# Safety_Loops.net
KiCad netlist of a schematic drawn in Altium Designer
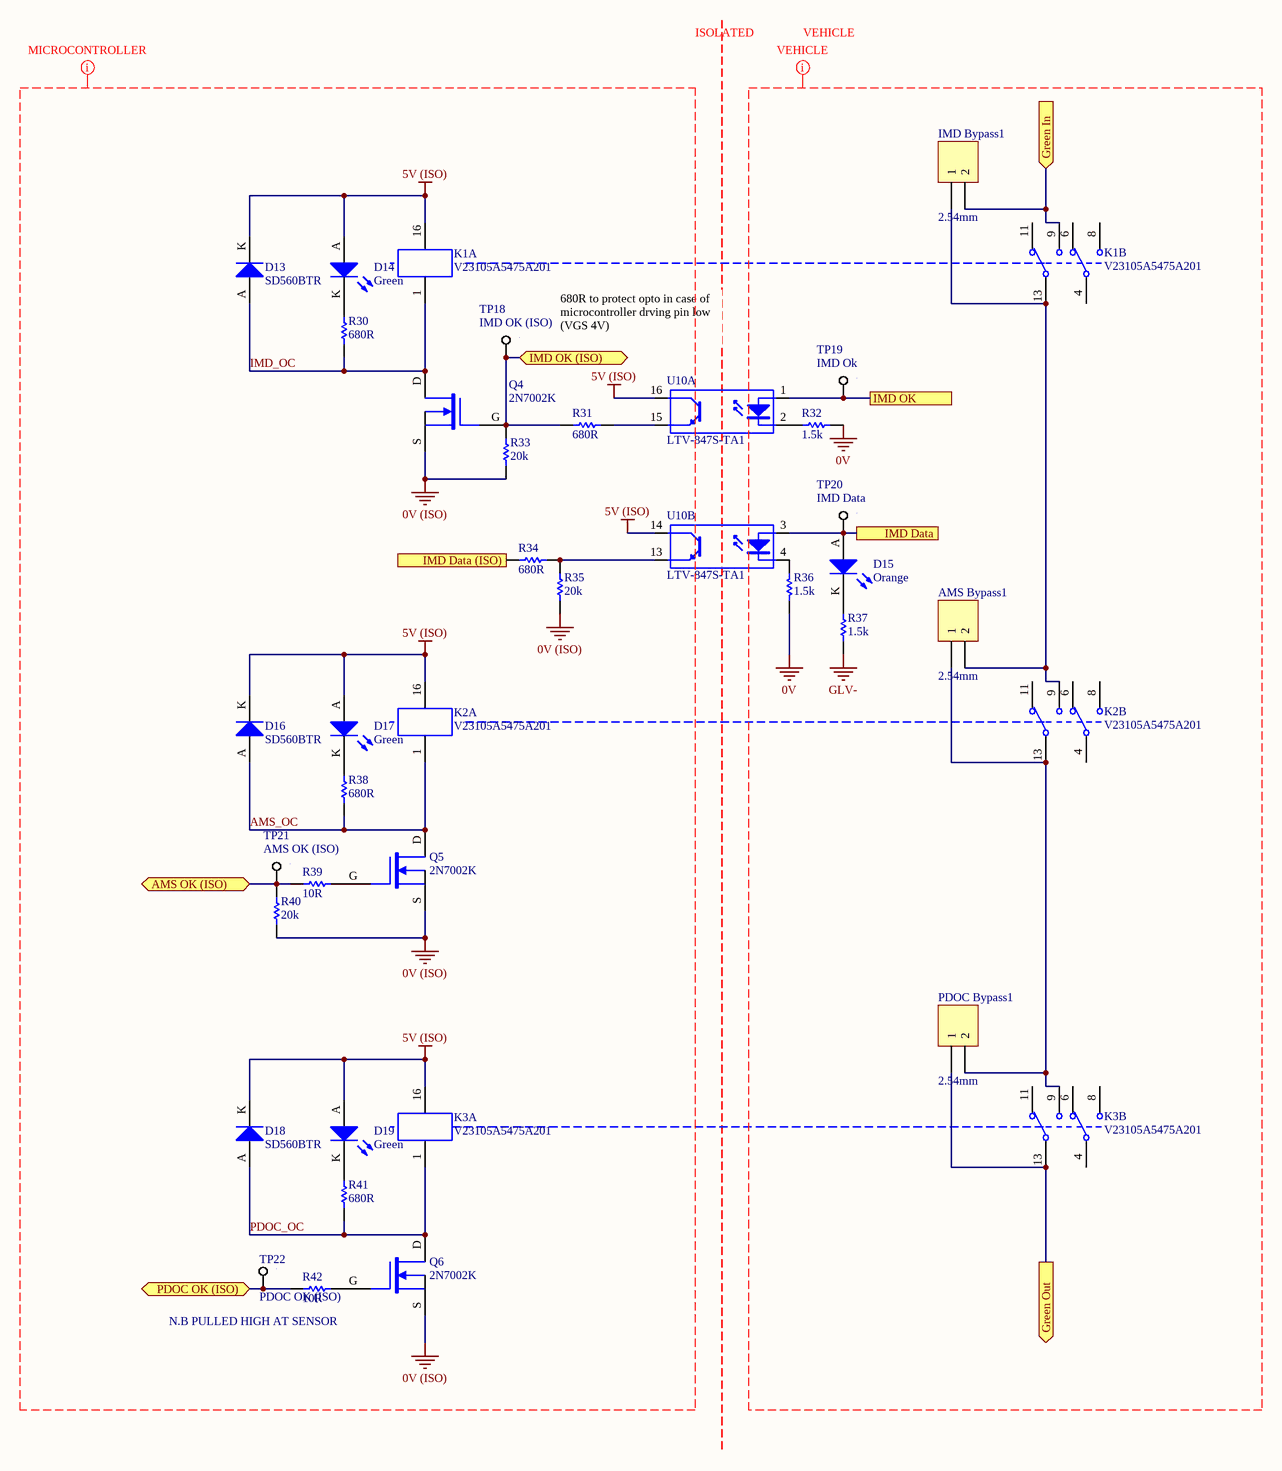
[diagram p0: Safety Loops.SchDoc]

(export (version "E")
  (design (tool "Eeschema 10.0.6"))
  (components
    (comp (ref "AMS Bypass1")
      (value "2.54mm")
      (footprint "TH 2.54mm Header 1x2")
      (fields (field (name "PART NUMBER") "TH 2.54mm Header 1x2") (field (name "CONTACT") "NA"))
      (libsource (lib "ts_20-standard-connectors") (part "Header 1x2"))
    )
    (comp (ref "D13")
      (value "SD560BTR")
      (footprint "SMB Diode")
      (description "1.2V_F 600V 5A SMB")
      (fields
        (field (name "MANUFACTURER") "SMC Diode Solutions")
        (field (name "DIGIKEY PART NUMBER") "1655-1530-2-ND")
      )
      (libsource (lib "ts_20-standard-library") (part "Diode"))
    )
    (comp (ref "D14")
      (value "Green")
      (footprint "0805 LED")
      (description "Green LED Indication - Discrete 1.75V 0805 (2012 Metric)")
      (fields (field (name "PART NUMBER") "SML-210FTT86") (field (name "MANUFACTURER") "ROHM Semiconductor"))
      (libsource (lib "ts_20-standard-library") (part "LED"))
    )
    (comp (ref "D15")
      (value "Orange")
      (footprint "0805 LED")
      (description "Orange LED Indication - Discrete 1.75V 0805 (2012 Metric)")
      (fields (field (name "PART NUMBER") "SML-211DTT86") (field (name "MANUFACTURER") "ROHM Semiconductor"))
      (libsource (lib "ts_20-standard-library") (part "LED"))
    )
    (comp (ref "D16")
      (value "SD560BTR")
      (footprint "SMB Diode")
      (description "1.2V_F 600V 5A SMB")
      (fields
        (field (name "MANUFACTURER") "SMC Diode Solutions")
        (field (name "DIGIKEY PART NUMBER") "1655-1530-2-ND")
      )
      (libsource (lib "ts_20-standard-library") (part "Diode"))
    )
    (comp (ref "D17")
      (value "Green")
      (footprint "0805 LED")
      (description "Green LED Indication - Discrete 1.75V 0805 (2012 Metric)")
      (fields (field (name "PART NUMBER") "SML-210FTT86") (field (name "MANUFACTURER") "ROHM Semiconductor"))
      (libsource (lib "ts_20-standard-library") (part "LED"))
    )
    (comp (ref "D18")
      (value "SD560BTR")
      (footprint "SMB Diode")
      (description "1.2V_F 600V 5A SMB")
      (fields
        (field (name "MANUFACTURER") "SMC Diode Solutions")
        (field (name "DIGIKEY PART NUMBER") "1655-1530-2-ND")
      )
      (libsource (lib "ts_20-standard-library") (part "Diode"))
    )
    (comp (ref "D19")
      (value "Green")
      (footprint "0805 LED")
      (description "Green LED Indication - Discrete 1.75V 0805 (2012 Metric)")
      (fields (field (name "PART NUMBER") "SML-210FTT86") (field (name "MANUFACTURER") "ROHM Semiconductor"))
      (libsource (lib "ts_20-standard-library") (part "LED"))
    )
    (comp (ref "IMD Bypass1")
      (value "2.54mm")
      (footprint "TH 2.54mm Header 1x2")
      (fields (field (name "PART NUMBER") "TH 2.54mm Header 1x2") (field (name "CONTACT") "NA"))
      (libsource (lib "ts_20-standard-connectors") (part "Header 1x2"))
    )
    (comp (ref "K1")
      (value "V23105A5475A201")
      (footprint "TI 2-DIL")
      (description "5V DPDT Relay 3A 220VDC")
      (fields (field (name "MANUFACTURER") "Axicom") (field (name "DIGIKEY PART NUMBER") "PB383-ND"))
      (libsource (lib "") (part "V23105A5475A201_1"))
    )
    (comp (ref "K2")
      (value "V23105A5475A201")
      (footprint "TI 2-DIL")
      (description "5V DPDT Relay 3A 220VDC")
      (fields (field (name "MANUFACTURER") "Axicom") (field (name "DIGIKEY PART NUMBER") "PB383-ND"))
      (libsource (lib "ts_20-standard-library") (part "V23105A5475A201"))
    )
    (comp (ref "K3")
      (value "V23105A5475A201")
      (footprint "TI 2-DIL")
      (description "5V DPDT Relay 3A 220VDC")
      (fields (field (name "MANUFACTURER") "Axicom") (field (name "DIGIKEY PART NUMBER") "PB383-ND"))
      (libsource (lib "ts_20-standard-library") (part "V23105A5475A201"))
    )
    (comp (ref "PDOC Bypass1")
      (value "2.54mm")
      (footprint "TH 2.54mm Header 1x2")
      (fields (field (name "PART NUMBER") "TH 2.54mm Header 1x2") (field (name "CONTACT") "NA"))
      (libsource (lib "ts_20-standard-connectors") (part "Header 1x2"))
    )
    (comp (ref "Q4")
      (value "2N7002K")
      (footprint "ON SOT-23 MOSFET")
      (description "60V 380mA, NFET MOSTFET (Small Signal)")
      (fields
        (field (name "MANUFACTURER") "ON Semiconductor")
        (field (name "DIGIKEY PART NUMBER") "2N7002KCT-ND")
        (field (name "PUBLISHER") "Altium Limited")
      )
      (libsource (lib "ts_20-standard-library") (part "MOSFET-N"))
    )
    (comp (ref "Q5")
      (value "2N7002K")
      (footprint "ON SOT-23 MOSFET")
      (description "60V 380mA, NFET MOSTFET (Small Signal)")
      (fields
        (field (name "MANUFACTURER") "ON Semiconductor")
        (field (name "DIGIKEY PART NUMBER") "2N7002KCT-ND")
        (field (name "PUBLISHER") "Altium Limited")
      )
      (libsource (lib "ts_20-standard-library") (part "MOSFET-N"))
    )
    (comp (ref "Q6")
      (value "2N7002K")
      (footprint "ON SOT-23 MOSFET")
      (description "60V 380mA, NFET MOSTFET (Small Signal)")
      (fields
        (field (name "MANUFACTURER") "ON Semiconductor")
        (field (name "DIGIKEY PART NUMBER") "2N7002KCT-ND")
        (field (name "PUBLISHER") "Altium Limited")
      )
      (libsource (lib "ts_20-standard-library") (part "MOSFET-N"))
    )
    (comp (ref "R30")
      (value "680R")
      (footprint "0805")
      (fields
        (field (name "PART NUMBER") "RC0805FR07680RL")
        (field (name "MANUFACTURER") "YAGEO")
        (field (name "TOLERANCE") "0.01")
      )
      (libsource (lib "ts_20-standard-library") (part "Resistor"))
    )
    (comp (ref "R31")
      (value "680R")
      (footprint "0805")
      (fields
        (field (name "PART NUMBER") "RC0805FR07680RL")
        (field (name "MANUFACTURER") "YAGEO")
        (field (name "TOLERANCE") "0.01")
      )
      (libsource (lib "ts_20-standard-library") (part "Resistor"))
    )
    (comp (ref "R32")
      (value "1.5k")
      (footprint "0805")
      (fields
        (field (name "PART NUMBER") "RC0805FR071K5L")
        (field (name "MANUFACTURER") "YAGEO")
        (field (name "TOLERANCE") "0.01")
      )
      (libsource (lib "ts_20-standard-library") (part "Resistor"))
    )
    (comp (ref "R33")
      (value "20k")
      (footprint "0805")
      (fields
        (field (name "PART NUMBER") "RC0805FR0720KL")
        (field (name "MANUFACTURER") "YAGEO")
        (field (name "TOLERANCE") "0.01")
      )
      (libsource (lib "ts_20-standard-library") (part "Resistor"))
    )
    (comp (ref "R34")
      (value "680R")
      (footprint "0805")
      (fields
        (field (name "PART NUMBER") "RC0805FR07680RL")
        (field (name "MANUFACTURER") "YAGEO")
        (field (name "TOLERANCE") "0.01")
      )
      (libsource (lib "ts_20-standard-library") (part "Resistor"))
    )
    (comp (ref "R35")
      (value "20k")
      (footprint "0805")
      (fields
        (field (name "PART NUMBER") "RC0805FR0720KL")
        (field (name "MANUFACTURER") "YAGEO")
        (field (name "TOLERANCE") "0.01")
      )
      (libsource (lib "ts_20-standard-library") (part "Resistor"))
    )
    (comp (ref "R36")
      (value "1.5k")
      (footprint "0805")
      (fields
        (field (name "PART NUMBER") "RC0805FR071K5L")
        (field (name "MANUFACTURER") "YAGEO")
        (field (name "TOLERANCE") "0.01")
      )
      (libsource (lib "ts_20-standard-library") (part "Resistor"))
    )
    (comp (ref "R37")
      (value "1.5k")
      (footprint "0805")
      (fields
        (field (name "PART NUMBER") "RC0805FR071K5L")
        (field (name "MANUFACTURER") "YAGEO")
        (field (name "TOLERANCE") "0.01")
      )
      (libsource (lib "ts_20-standard-library") (part "Resistor"))
    )
    (comp (ref "R38")
      (value "680R")
      (footprint "0805")
      (fields
        (field (name "PART NUMBER") "RC0805FR07680RL")
        (field (name "MANUFACTURER") "YAGEO")
        (field (name "TOLERANCE") "0.01")
      )
      (libsource (lib "ts_20-standard-library") (part "Resistor"))
    )
    (comp (ref "R39")
      (value "10R")
      (footprint "0805")
      (fields
        (field (name "PART NUMBER") "RC0805FR0710RL")
        (field (name "MANUFACTURER") "YAGEO")
        (field (name "TOLERANCE") "0.01")
      )
      (libsource (lib "ts_20-standard-library") (part "Resistor"))
    )
    (comp (ref "R40")
      (value "20k")
      (footprint "0805")
      (fields
        (field (name "PART NUMBER") "RC0805FR0720KL")
        (field (name "MANUFACTURER") "YAGEO")
        (field (name "TOLERANCE") "0.01")
      )
      (libsource (lib "ts_20-standard-library") (part "Resistor"))
    )
    (comp (ref "R41")
      (value "680R")
      (footprint "0805")
      (fields
        (field (name "PART NUMBER") "RC0805FR07680RL")
        (field (name "MANUFACTURER") "YAGEO")
        (field (name "TOLERANCE") "0.01")
      )
      (libsource (lib "ts_20-standard-library") (part "Resistor"))
    )
    (comp (ref "R42")
      (value "10R")
      (footprint "0805")
      (fields
        (field (name "PART NUMBER") "RC0805FR0710RL")
        (field (name "MANUFACTURER") "YAGEO")
        (field (name "TOLERANCE") "0.01")
      )
      (libsource (lib "ts_20-standard-library") (part "Resistor"))
    )
    (comp (ref "TP18")
      (value "IMD OK (ISO)")
      (footprint "SMD Test Point 1mm")
      (fields (field (name "PART NUMBER") "SMD Test Point Small") (field (name "CONTACT") "NA"))
      (libsource (lib "ts_20-standard-connectors") (part "Test Point Small"))
    )
    (comp (ref "TP19")
      (value "IMD Ok")
      (footprint "SMD Test Point 1mm")
      (fields (field (name "PART NUMBER") "SMD Test Point Small") (field (name "CONTACT") "NA"))
      (libsource (lib "ts_20-standard-connectors") (part "Test Point Small"))
    )
    (comp (ref "TP20")
      (value "IMD Data")
      (footprint "SMD Test Point 1mm")
      (fields (field (name "PART NUMBER") "SMD Test Point Small") (field (name "CONTACT") "NA"))
      (libsource (lib "ts_20-standard-connectors") (part "Test Point Small"))
    )
    (comp (ref "TP21")
      (value "AMS OK (ISO)")
      (footprint "SMD Test Point 1mm")
      (fields (field (name "PART NUMBER") "SMD Test Point Small") (field (name "CONTACT") "NA"))
      (libsource (lib "ts_20-standard-connectors") (part "Test Point Small"))
    )
    (comp (ref "TP22")
      (value "PDOC OK (ISO)")
      (footprint "SMD Test Point 1mm")
      (fields (field (name "PART NUMBER") "SMD Test Point Small") (field (name "CONTACT") "NA"))
      (libsource (lib "ts_20-standard-connectors") (part "Test Point Small"))
    )
    (comp (ref "U10")
      (value "LTV-847S-TA1")
      (footprint "ON 16-SMD")
      (description "Optoisolator Transistor Output 5000Vrms 4 Channel 16-SMD")
      (fields
        (field (name "MANUFACTURER") "Lite-On Inc")
        (field (name "DIGIKEY PART NUMBER") "160-1371-5-ND")
      )
      (libsource (lib "ts_20-standard-library") (part "LTV-847S-TA1"))
    )
  )
  (nets
    (net (code "1") (name "/AMS OK (ISO)") (class "Default")
      (node (ref "R39") (pin "1") (pinfunction "1_1") (pintype "passive"))
      (node (ref "R40") (pin "2") (pinfunction "2_2") (pintype "passive"))
      (node (ref "TP21") (pin "1") (pinfunction "1_1") (pintype "passive"))
    )
    (net (code "2") (name "/AMS_OC") (class "Default")
      (node (ref "D16") (pin "A") (pinfunction "A_A") (pintype "passive"))
      (node (ref "K2") (pin "1") (pinfunction "1_1") (pintype "passive"))
      (node (ref "Q5") (pin "D") (pinfunction "D_D") (pintype "passive"))
      (node (ref "R38") (pin "1") (pinfunction "1_1") (pintype "passive"))
    )
    (net (code "3") (name "/Green In") (class "Default")
      (node (ref "IMD Bypass1") (pin "2") (pinfunction "2_2") (pintype "passive"))
      (node (ref "K1") (pin "9") (pinfunction "9_9") (pintype "passive"))
    )
    (net (code "4") (name "/Green Out") (class "Default")
      (node (ref "K3") (pin "13") (pinfunction "13_13") (pintype "passive"))
      (node (ref "PDOC Bypass1") (pin "1") (pinfunction "1_1") (pintype "passive"))
    )
    (net (code "5") (name "/IMD Data") (class "Default")
      (node (ref "D15") (pin "A") (pinfunction "A_A") (pintype "passive"))
      (node (ref "TP20") (pin "1") (pinfunction "1_1") (pintype "passive"))
      (node (ref "U10") (pin "3") (pinfunction "A_3") (pintype "passive"))
    )
    (net (code "6") (name "/IMD Data (ISO)") (class "Default")
      (node (ref "R34") (pin "1") (pinfunction "1_1") (pintype "passive"))
    )
    (net (code "7") (name "/IMD OK") (class "Default")
      (node (ref "TP19") (pin "1") (pinfunction "1_1") (pintype "passive"))
      (node (ref "U10") (pin "1") (pinfunction "A_1") (pintype "passive"))
    )
    (net (code "8") (name "/IMD OK (ISO)") (class "Default")
      (node (ref "Q4") (pin "G") (pinfunction "G_G") (pintype "passive"))
      (node (ref "R31") (pin "1") (pinfunction "1_1") (pintype "passive"))
      (node (ref "R33") (pin "2") (pinfunction "2_2") (pintype "passive"))
      (node (ref "TP18") (pin "1") (pinfunction "1_1") (pintype "passive"))
    )
    (net (code "9") (name "/IMD_OC") (class "Default")
      (node (ref "D13") (pin "A") (pinfunction "A_A") (pintype "passive"))
      (node (ref "K1") (pin "1") (pinfunction "1_1") (pintype "passive"))
      (node (ref "Q4") (pin "D") (pinfunction "D_D") (pintype "passive"))
      (node (ref "R30") (pin "1") (pinfunction "1_1") (pintype "passive"))
    )
    (net (code "10") (name "/PDOC OK (ISO)") (class "Default")
      (node (ref "R42") (pin "1") (pinfunction "1_1") (pintype "passive"))
      (node (ref "TP22") (pin "1") (pinfunction "1_1") (pintype "passive"))
    )
    (net (code "11") (name "/PDOC_OC") (class "Default")
      (node (ref "D18") (pin "A") (pinfunction "A_A") (pintype "passive"))
      (node (ref "K3") (pin "1") (pinfunction "1_1") (pintype "passive"))
      (node (ref "Q6") (pin "D") (pinfunction "D_D") (pintype "passive"))
      (node (ref "R41") (pin "1") (pinfunction "1_1") (pintype "passive"))
    )
    (net (code "12") (name "0V") (class "Default")
      (node (ref "R32") (pin "1") (pinfunction "1_1") (pintype "passive"))
      (node (ref "R36") (pin "2") (pinfunction "2_2") (pintype "passive"))
    )
    (net (code "13") (name "0V (ISO)") (class "Default")
      (node (ref "Q4") (pin "S") (pinfunction "S_S") (pintype "passive"))
      (node (ref "Q5") (pin "S") (pinfunction "S_S") (pintype "passive"))
      (node (ref "Q6") (pin "S") (pinfunction "S_S") (pintype "passive"))
      (node (ref "R33") (pin "1") (pinfunction "1_1") (pintype "passive"))
      (node (ref "R35") (pin "1") (pinfunction "1_1") (pintype "passive"))
      (node (ref "R40") (pin "1") (pinfunction "1_1") (pintype "passive"))
    )
    (net (code "14") (name "5V (ISO)") (class "Default")
      (node (ref "D13") (pin "K") (pinfunction "K_K") (pintype "passive"))
      (node (ref "D14") (pin "A") (pinfunction "A_A") (pintype "passive"))
      (node (ref "D16") (pin "K") (pinfunction "K_K") (pintype "passive"))
      (node (ref "D17") (pin "A") (pinfunction "A_A") (pintype "passive"))
      (node (ref "D18") (pin "K") (pinfunction "K_K") (pintype "passive"))
      (node (ref "D19") (pin "A") (pinfunction "A_A") (pintype "passive"))
      (node (ref "K1") (pin "16") (pinfunction "16_16") (pintype "passive"))
      (node (ref "K2") (pin "16") (pinfunction "16_16") (pintype "passive"))
      (node (ref "K3") (pin "16") (pinfunction "16_16") (pintype "passive"))
      (node (ref "U10") (pin "14") (pinfunction "C_14") (pintype "passive"))
      (node (ref "U10") (pin "16") (pinfunction "C_16") (pintype "passive"))
    )
    (net (code "15") (name "GLV-") (class "Default")
      (node (ref "R37") (pin "2") (pinfunction "2_2") (pintype "passive"))
    )
    (net (code "16") (name "Net-(AMS Bypass1-Pad1)") (class "Default")
      (node (ref "AMS Bypass1") (pin "1") (pinfunction "1_1") (pintype "passive"))
      (node (ref "K2") (pin "13") (pinfunction "13_13") (pintype "passive"))
      (node (ref "K3") (pin "9") (pinfunction "9_9") (pintype "passive"))
      (node (ref "PDOC Bypass1") (pin "2") (pinfunction "2_2") (pintype "passive"))
    )
    (net (code "17") (name "Net-(AMS Bypass1-Pad2)") (class "Default")
      (node (ref "AMS Bypass1") (pin "2") (pinfunction "2_2") (pintype "passive"))
      (node (ref "IMD Bypass1") (pin "1") (pinfunction "1_1") (pintype "passive"))
      (node (ref "K1") (pin "13") (pinfunction "13_13") (pintype "passive"))
      (node (ref "K2") (pin "9") (pinfunction "9_9") (pintype "passive"))
    )
    (net (code "18") (name "Net-(D14-PadK)") (class "Default")
      (node (ref "D14") (pin "K") (pinfunction "K_K") (pintype "passive"))
      (node (ref "R30") (pin "2") (pinfunction "2_2") (pintype "passive"))
    )
    (net (code "19") (name "Net-(D15-PadK)") (class "Default")
      (node (ref "D15") (pin "K") (pinfunction "K_K") (pintype "passive"))
      (node (ref "R37") (pin "1") (pinfunction "1_1") (pintype "passive"))
    )
    (net (code "20") (name "Net-(D17-PadK)") (class "Default")
      (node (ref "D17") (pin "K") (pinfunction "K_K") (pintype "passive"))
      (node (ref "R38") (pin "2") (pinfunction "2_2") (pintype "passive"))
    )
    (net (code "21") (name "Net-(D19-PadK)") (class "Default")
      (node (ref "D19") (pin "K") (pinfunction "K_K") (pintype "passive"))
      (node (ref "R41") (pin "2") (pinfunction "2_2") (pintype "passive"))
    )
    (net (code "22") (name "Net-(Q5-PadG)") (class "Default")
      (node (ref "Q5") (pin "G") (pinfunction "G_G") (pintype "passive"))
      (node (ref "R39") (pin "2") (pinfunction "2_2") (pintype "passive"))
    )
    (net (code "23") (name "Net-(Q6-PadG)") (class "Default")
      (node (ref "Q6") (pin "G") (pinfunction "G_G") (pintype "passive"))
      (node (ref "R42") (pin "2") (pinfunction "2_2") (pintype "passive"))
    )
    (net (code "24") (name "Net-(U10A-E)") (class "Default")
      (node (ref "R31") (pin "2") (pinfunction "2_2") (pintype "passive"))
      (node (ref "U10") (pin "15") (pinfunction "E_15") (pintype "passive"))
    )
    (net (code "25") (name "Net-(U10A-K)") (class "Default")
      (node (ref "R32") (pin "2") (pinfunction "2_2") (pintype "passive"))
      (node (ref "U10") (pin "2") (pinfunction "K_2") (pintype "passive"))
    )
    (net (code "26") (name "Net-(U10B-E)") (class "Default")
      (node (ref "R34") (pin "2") (pinfunction "2_2") (pintype "passive"))
      (node (ref "R35") (pin "2") (pinfunction "2_2") (pintype "passive"))
      (node (ref "U10") (pin "13") (pinfunction "E_13") (pintype "passive"))
    )
    (net (code "27") (name "Net-(U10B-K)") (class "Default")
      (node (ref "R36") (pin "1") (pinfunction "1_1") (pintype "passive"))
      (node (ref "U10") (pin "4") (pinfunction "K_4") (pintype "passive"))
    )
    (net (code "28") (name "unconnected-(K1-Pad4)") (class "Default")
      (node (ref "K1") (pin "4") (pinfunction "4_4") (pintype "passive"))
    )
    (net (code "29") (name "unconnected-(K1-Pad6)") (class "Default")
      (node (ref "K1") (pin "6") (pinfunction "6_6") (pintype "passive"))
    )
    (net (code "30") (name "unconnected-(K1-Pad8)") (class "Default")
      (node (ref "K1") (pin "8") (pinfunction "8_8") (pintype "passive"))
    )
    (net (code "31") (name "unconnected-(K1-Pad11)") (class "Default")
      (node (ref "K1") (pin "11") (pinfunction "11_11") (pintype "passive"))
    )
    (net (code "32") (name "unconnected-(K2-Pad4)") (class "Default")
      (node (ref "K2") (pin "4") (pinfunction "4_4") (pintype "passive"))
    )
    (net (code "33") (name "unconnected-(K2-Pad6)") (class "Default")
      (node (ref "K2") (pin "6") (pinfunction "6_6") (pintype "passive"))
    )
    (net (code "34") (name "unconnected-(K2-Pad8)") (class "Default")
      (node (ref "K2") (pin "8") (pinfunction "8_8") (pintype "passive"))
    )
    (net (code "35") (name "unconnected-(K2-Pad11)") (class "Default")
      (node (ref "K2") (pin "11") (pinfunction "11_11") (pintype "passive"))
    )
    (net (code "36") (name "unconnected-(K3-Pad4)") (class "Default")
      (node (ref "K3") (pin "4") (pinfunction "4_4") (pintype "passive"))
    )
    (net (code "37") (name "unconnected-(K3-Pad6)") (class "Default")
      (node (ref "K3") (pin "6") (pinfunction "6_6") (pintype "passive"))
    )
    (net (code "38") (name "unconnected-(K3-Pad8)") (class "Default")
      (node (ref "K3") (pin "8") (pinfunction "8_8") (pintype "passive"))
    )
    (net (code "39") (name "unconnected-(K3-Pad11)") (class "Default")
      (node (ref "K3") (pin "11") (pinfunction "11_11") (pintype "passive"))
    )
  )
)
